# current_mirror.net
KiCad netlist of a schematic drawn in Altium Designer
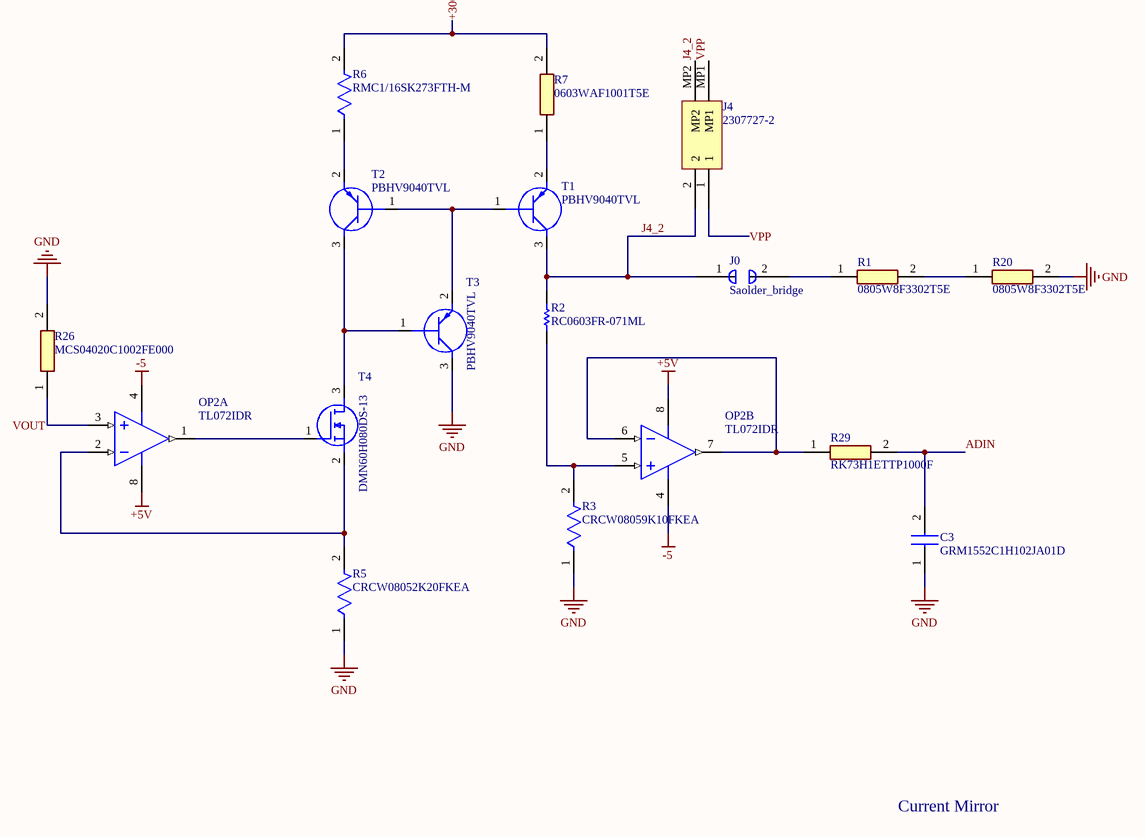
[diagram p0: current_mirror.SchDoc]

(export (version "E")
  (design (tool "Eeschema 10.0.6"))
  (components
    (comp (ref "C3")
      (value "GRM1552C1H102JA01D")
      (footprint "SamacSys:CAPC1005X70N")
      (description "Capacitor")
      (libsource (lib "*") (part "GRM1552C1H102JA01D"))
    )
    (comp (ref "J0")
      (value "Saolder_bridge")
      (footprint "Solder Bridge")
      (libsource (lib "solder_bridge") (part "Component_1"))
    )
    (comp (ref "J4")
      (value "2307727-2")
      (footprint "SamacSys:2307727-2")
      (description "Connector")
      (libsource (lib "SamacSys") (part "2307727-2"))
    )
    (comp (ref "OP2")
      (value "TL072IDR")
      (footprint "D0008A_L")
      (fields (field (name "MANUFACTURER") "Texas Instruments"))
      (libsource (lib "Altium Content Vault") (part "TI-AMP-D6-2-8_D"))
    )
    (comp (ref "R1")
      (value "0805W8F3302T5E")
      (footprint "SamacSys:RESC2013X65N")
      (description "Resistor")
      (libsource (lib "*") (part "0805W8F3302T5E"))
    )
    (comp (ref "R2")
      (value "RC0603FR-071ML")
      (footprint "RESC1608X55X25LL10T15")
      (description "Chip Resistor, 1 MOhm, +/- 1%, 100 mW, -55 to 155 degC, 0603 (1608 Metric), RoHS, Tape and Reel")
      (fields (field (name "TOLERANCE") "20%"))
      (libsource (lib "Altium Content Vault") (part "RES-2"))
    )
    (comp (ref "R3")
      (value "CRCW08059K10FKEA")
      (footprint "FP-CRCW0805-e3-IPC_C")
      (description "RES Thick Film, 9.1kΩ, 1%, 0.125W, 100ppm/°C, 0805")
      (fields (field (name "TOLERANCE") "1%"))
      (libsource (lib "Altium Content Vault") (part "1029c3af85768c4190bb7ad29bc67b5"))
    )
    (comp (ref "R5")
      (value "CRCW08052K20FKEA")
      (footprint "FP-CRCW0805-e3-IPC_B")
      (description "RES Thick Film, 2.2kΩ, 1%, 0.125W, 100ppm/°C, 0805")
      (fields (field (name "TOLERANCE") "1%"))
      (libsource (lib "Altium Content Vault") (part "1029c3af85768c4190bb7ad29bc67b5"))
    )
    (comp (ref "R6")
      (value "RMC1/16SK273FTH-M")
      (footprint "FP-CRCW0402-e3-IPC_A")
      (description "RES Thick Film, 27kΩ, 1%, 0.063W, 100ppm/°C, 0402")
      (fields (field (name "TOLERANCE") "1%"))
      (libsource (lib "Altium Content Vault") (part "1029c3af85768c4190bb7ad29bc67b5"))
    )
    (comp (ref "R7")
      (value "0603WAF1001T5E")
      (footprint "SamacSys:RESC1608X55N")
      (description "Resistor")
      (libsource (lib "*") (part "0603WAF1001T5E"))
    )
    (comp (ref "R20")
      (value "0805W8F3302T5E")
      (footprint "SamacSys:RESC2013X65N")
      (description "Resistor")
      (libsource (lib "*") (part "0805W8F3302T5E"))
    )
    (comp (ref "R26")
      (value "MCS04020C1002FE000")
      (footprint "SamacSys:RESC1005X37N")
      (description "Resistor")
      (fields (field (name "MOUSER PART NUMBER") "594-MCS04020C1002FE0"))
      (libsource (lib "*") (part "MCS04020C1002FE000"))
    )
    (comp (ref "R29")
      (value "RK73H1ETTP1000F")
      (footprint "SamacSys:RESC1005X40N")
      (description "Resistor")
      (fields (field (name "MOUSER PART NUMBER") "660-RK73H1ETTP1000F"))
      (libsource (lib "*") (part "RK73H1ETTP1000F"))
    )
    (comp (ref "T1")
      (value "PBHV9040TVL")
      (footprint "SamacSys:SOT95P230X110-3N")
      (description "Transistor BJT PNP")
      (fields (field (name "MOUSER PART NUMBER") "771-PBHV9040TVL"))
      (libsource (lib "*") (part "PBHV9040TVL"))
    )
    (comp (ref "T2")
      (value "PBHV9040TVL")
      (footprint "SamacSys:SOT95P230X110-3N")
      (description "Transistor BJT PNP")
      (fields (field (name "MOUSER PART NUMBER") "771-PBHV9040TVL"))
      (libsource (lib "*") (part "PBHV9040TVL"))
    )
    (comp (ref "T3")
      (value "PBHV9040TVL")
      (footprint "SamacSys:SOT95P230X110-3N")
      (description "Transistor BJT PNP")
      (fields (field (name "MOUSER PART NUMBER") "771-PBHV9040TVL"))
      (libsource (lib "*") (part "PBHV9040TVL"))
    )
    (comp (ref "T4")
      (value "DMN60H080DS-13")
      (footprint "SamacSys:SOT96P240X110-3N")
      (description "MOSFET (N-Channel)")
      (fields (field (name "MOUSER PART NUMBER") "621-DMN60H080DS-13"))
      (libsource (lib "*") (part "DMN60H080DS-13"))
    )
  )
  (nets
    (net (code "1") (name "+5V") (class "Default")
      (node (ref "OP2") (pin "8") (pinfunction "VCC+_8") (pintype "power_in"))
    )
    (net (code "2") (name "-5") (class "Default")
      (node (ref "OP2") (pin "4") (pinfunction "VCC-_4") (pintype "passive"))
    )
    (net (code "3") (name "/+300V") (class "Default")
      (node (ref "R6") (pin "2") (pinfunction "2_2") (pintype "passive"))
      (node (ref "R7") (pin "2") (pinfunction "2_2") (pintype "passive"))
    )
    (net (code "4") (name "/ADIN") (class "Default")
      (node (ref "C3") (pin "2") (pinfunction "2_2") (pintype "passive"))
      (node (ref "R29") (pin "2") (pinfunction "2_2") (pintype "passive"))
    )
    (net (code "5") (name "/J4_2") (class "Default")
      (node (ref "J0") (pin "1") (pinfunction "1_1") (pintype "passive"))
      (node (ref "J4") (pin "2") (pinfunction "2_2") (pintype "passive"))
      (node (ref "J4") (pin "MP2") (pinfunction "MP2_MP2") (pintype "passive"))
      (node (ref "R2") (pin "2") (pinfunction "2_2") (pintype "passive"))
      (node (ref "T1") (pin "3") (pinfunction "C_3") (pintype "passive"))
    )
    (net (code "6") (name "/VOUT") (class "Default")
      (node (ref "OP2") (pin "3") (pinfunction "IN1+_3") (pintype "input"))
      (node (ref "R26") (pin "1") (pinfunction "1_1") (pintype "passive"))
    )
    (net (code "7") (name "/VPP") (class "Default")
      (node (ref "J4") (pin "1") (pinfunction "1_1") (pintype "passive"))
      (node (ref "J4") (pin "MP1") (pinfunction "MP1_MP1") (pintype "passive"))
    )
    (net (code "8") (name "GND") (class "Default")
      (node (ref "C3") (pin "1") (pinfunction "1_1") (pintype "passive"))
      (node (ref "R20") (pin "2") (pinfunction "2_2") (pintype "passive"))
      (node (ref "R26") (pin "2") (pinfunction "2_2") (pintype "passive"))
      (node (ref "R3") (pin "1") (pinfunction "1_1") (pintype "passive"))
      (node (ref "R5") (pin "1") (pinfunction "1_1") (pintype "passive"))
      (node (ref "T3") (pin "3") (pinfunction "C_3") (pintype "passive"))
    )
    (net (code "9") (name "Net-(J0-Pad2)") (class "Default")
      (node (ref "J0") (pin "2") (pinfunction "2_2") (pintype "passive"))
      (node (ref "R1") (pin "1") (pinfunction "1_1") (pintype "passive"))
    )
    (net (code "10") (name "Net-(OP2A-IN1-)") (class "Default")
      (node (ref "OP2") (pin "2") (pinfunction "IN1-_2") (pintype "input"))
      (node (ref "R5") (pin "2") (pinfunction "2_2") (pintype "passive"))
      (node (ref "T4") (pin "2") (pinfunction "S_2") (pintype "passive"))
    )
    (net (code "11") (name "Net-(OP2A-OUT1)") (class "Default")
      (node (ref "OP2") (pin "1") (pinfunction "OUT1_1") (pintype "output"))
      (node (ref "T4") (pin "1") (pinfunction "G_1") (pintype "passive"))
    )
    (net (code "12") (name "Net-(OP2B-IN2+)") (class "Default")
      (node (ref "OP2") (pin "5") (pinfunction "IN2+_5") (pintype "input"))
      (node (ref "R2") (pin "1") (pinfunction "1_1") (pintype "passive"))
      (node (ref "R3") (pin "2") (pinfunction "2_2") (pintype "passive"))
    )
    (net (code "13") (name "Net-(OP2B-IN2-)") (class "Default")
      (node (ref "OP2") (pin "6") (pinfunction "IN2-_6") (pintype "input"))
      (node (ref "OP2") (pin "7") (pinfunction "OUT2_7") (pintype "output"))
      (node (ref "R29") (pin "1") (pinfunction "1_1") (pintype "passive"))
    )
    (net (code "14") (name "Net-(R1-Pad2)") (class "Default")
      (node (ref "R1") (pin "2") (pinfunction "2_2") (pintype "passive"))
      (node (ref "R20") (pin "1") (pinfunction "1_1") (pintype "passive"))
    )
    (net (code "15") (name "Net-(T1-B)") (class "Default")
      (node (ref "T1") (pin "1") (pinfunction "B_1") (pintype "passive"))
      (node (ref "T2") (pin "1") (pinfunction "B_1") (pintype "passive"))
      (node (ref "T3") (pin "2") (pinfunction "E_2") (pintype "passive"))
    )
    (net (code "16") (name "Net-(T1-E)") (class "Default")
      (node (ref "R7") (pin "1") (pinfunction "1_1") (pintype "passive"))
      (node (ref "T1") (pin "2") (pinfunction "E_2") (pintype "passive"))
    )
    (net (code "17") (name "Net-(T2-C)") (class "Default")
      (node (ref "T2") (pin "3") (pinfunction "C_3") (pintype "passive"))
      (node (ref "T3") (pin "1") (pinfunction "B_1") (pintype "passive"))
      (node (ref "T4") (pin "3") (pinfunction "D_3") (pintype "passive"))
    )
    (net (code "18") (name "Net-(T2-E)") (class "Default")
      (node (ref "R6") (pin "1") (pinfunction "1_1") (pintype "passive"))
      (node (ref "T2") (pin "2") (pinfunction "E_2") (pintype "passive"))
    )
  )
)
